# ExternalConnectors.net
KiCad netlist of a schematic drawn in Altium Designer
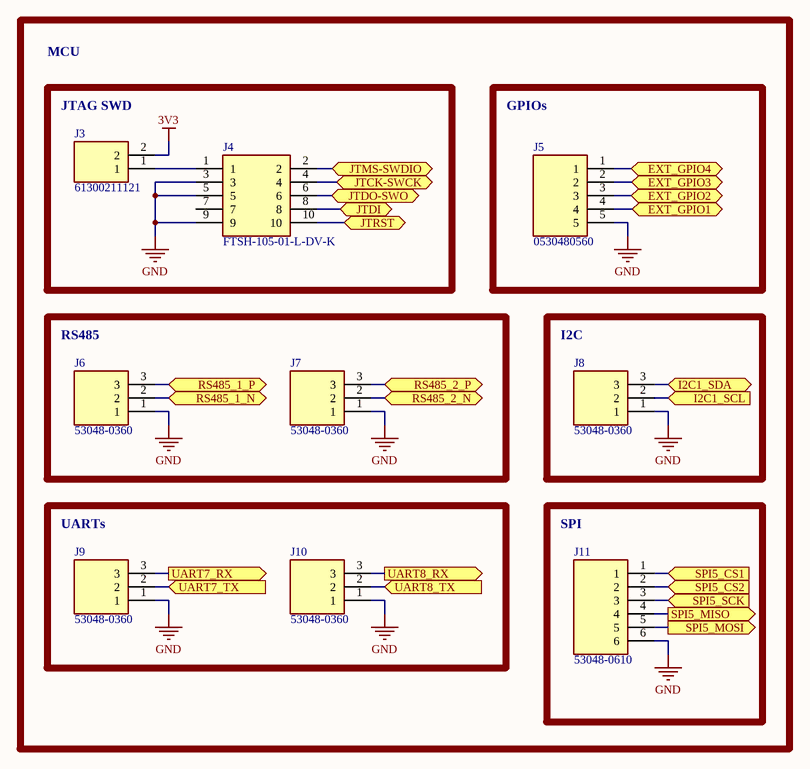
[diagram p0: ExternalConnectors.SchDoc]

(export (version "E")
  (design (tool "Eeschema 10.0.6"))
  (components
    (comp (ref "J3")
      (value "61300211121")
      (footprint "RT_IS:HDRV2W110P0X254_1X2_508X254X854P")
      (description "Connector")
      (fields (field (name "MOUSER PART NUMBER") "710-61300211121"))
      (libsource (lib "*") (part "61300211121"))
    )
    (comp (ref "J4")
      (value "FTSH-105-01-L-DV-K")
      (footprint "RT_IS:FTSH10501LDVK")
      (description "Connector Header Surface Mount 10 position 0.050\" (1.27mm)")
      (fields (field (name "MOUSER PART NUMBER") "200-FTSH10501LDVK"))
      (libsource (lib "*") (part "FTSH-105-01-L-DV-K"))
    )
    (comp (ref "J5")
      (value "0530480560")
      (footprint "RT_IS:530480510")
      (description "Connector Header Through Hole, Right Angle 5 position 0.049\" (1.25mm)")
      (fields
        (field (name "MANUFACTURER_PART_NUMBER") "53048-0510")
        (field (name "MOUSER PART NUMBER") "538-53048-0510")
      )
      (libsource (lib "*") (part "53048-0510"))
    )
    (comp (ref "J6")
      (value "53048-0360")
      (footprint "RT_IS:SHDRRA3W35P0X125_1X3_550X550X350P")
      (description "Connector Header Through Hole, Right Angle 3 position 0.049\" (1.25mm)")
      (fields
        (field (name "MANUFACTURER_PART_NUMBER") "53048-0310")
        (field (name "MOUSER PART NUMBER") "538-53048-0310")
      )
      (libsource (lib "*") (part "53048-0310"))
    )
    (comp (ref "J7")
      (value "53048-0360")
      (footprint "RT_IS:SHDRRA3W35P0X125_1X3_550X550X350P")
      (description "Connector Header Through Hole, Right Angle 3 position 0.049\" (1.25mm)")
      (fields
        (field (name "MANUFACTURER_PART_NUMBER") "53048-0310")
        (field (name "MOUSER PART NUMBER") "538-53048-0310")
      )
      (libsource (lib "*") (part "53048-0310"))
    )
    (comp (ref "J8")
      (value "53048-0360")
      (footprint "RT_IS:SHDRRA3W35P0X125_1X3_550X550X350P")
      (description "Connector Header Through Hole, Right Angle 3 position 0.049\" (1.25mm)")
      (fields
        (field (name "MANUFACTURER_PART_NUMBER") "53048-0310")
        (field (name "MOUSER PART NUMBER") "538-53048-0310")
      )
      (libsource (lib "*") (part "53048-0310"))
    )
    (comp (ref "J9")
      (value "53048-0360")
      (footprint "RT_IS:SHDRRA3W35P0X125_1X3_550X550X350P")
      (description "Connector Header Through Hole, Right Angle 3 position 0.049\" (1.25mm)")
      (fields
        (field (name "MANUFACTURER_PART_NUMBER") "53048-0310")
        (field (name "MOUSER PART NUMBER") "538-53048-0310")
      )
      (libsource (lib "*") (part "53048-0310"))
    )
    (comp (ref "J10")
      (value "53048-0360")
      (footprint "RT_IS:SHDRRA3W35P0X125_1X3_550X550X350P")
      (description "Connector Header Through Hole, Right Angle 3 position 0.049\" (1.25mm)")
      (fields
        (field (name "MANUFACTURER_PART_NUMBER") "53048-0310")
        (field (name "MOUSER PART NUMBER") "538-53048-0310")
      )
      (libsource (lib "*") (part "53048-0310"))
    )
    (comp (ref "J11")
      (value "53048-0610")
      (footprint "530480610")
      (description "Connector")
      (fields (field (name "MOUSER PART NUMBER") "538-53048-0610"))
      (libsource (lib "*") (part "53048-0610"))
    )
  )
  (nets
    (net (code "1") (name "/EXT_GPIO1") (class "Default")
      (node (ref "J5") (pin "4") (pinfunction "4_4") (pintype "passive"))
    )
    (net (code "2") (name "/EXT_GPIO2") (class "Default")
      (node (ref "J5") (pin "3") (pinfunction "3_3") (pintype "passive"))
    )
    (net (code "3") (name "/EXT_GPIO3") (class "Default")
      (node (ref "J5") (pin "2") (pinfunction "2_2") (pintype "passive"))
    )
    (net (code "4") (name "/EXT_GPIO4") (class "Default")
      (node (ref "J5") (pin "1") (pinfunction "1_1") (pintype "passive"))
    )
    (net (code "5") (name "/I2C1_SCL") (class "Default")
      (node (ref "J8") (pin "2") (pinfunction "2_2") (pintype "passive"))
    )
    (net (code "6") (name "/I2C1_SDA") (class "Default")
      (node (ref "J8") (pin "3") (pinfunction "3_3") (pintype "passive"))
    )
    (net (code "7") (name "/JTCK-SWCK") (class "Default")
      (node (ref "J4") (pin "4") (pinfunction "4_4") (pintype "passive"))
    )
    (net (code "8") (name "/JTDI") (class "Default")
      (node (ref "J4") (pin "8") (pinfunction "8_8") (pintype "passive"))
    )
    (net (code "9") (name "/JTDO-SWO") (class "Default")
      (node (ref "J4") (pin "6") (pinfunction "6_6") (pintype "passive"))
    )
    (net (code "10") (name "/JTMS-SWDIO") (class "Default")
      (node (ref "J4") (pin "2") (pinfunction "2_2") (pintype "passive"))
    )
    (net (code "11") (name "/JTRST") (class "Default")
      (node (ref "J4") (pin "10") (pinfunction "10_10") (pintype "passive"))
    )
    (net (code "12") (name "/RS485_1_N") (class "Default")
      (node (ref "J6") (pin "2") (pinfunction "2_2") (pintype "passive"))
    )
    (net (code "13") (name "/RS485_1_P") (class "Default")
      (node (ref "J6") (pin "3") (pinfunction "3_3") (pintype "passive"))
    )
    (net (code "14") (name "/RS485_2_N") (class "Default")
      (node (ref "J7") (pin "2") (pinfunction "2_2") (pintype "passive"))
    )
    (net (code "15") (name "/RS485_2_P") (class "Default")
      (node (ref "J7") (pin "3") (pinfunction "3_3") (pintype "passive"))
    )
    (net (code "16") (name "/SPI5_CS1") (class "Default")
      (node (ref "J11") (pin "1") (pinfunction "1_1") (pintype "passive"))
    )
    (net (code "17") (name "/SPI5_CS2") (class "Default")
      (node (ref "J11") (pin "2") (pinfunction "2_2") (pintype "passive"))
    )
    (net (code "18") (name "/SPI5_MISO") (class "Default")
      (node (ref "J11") (pin "4") (pinfunction "4_4") (pintype "passive"))
    )
    (net (code "19") (name "/SPI5_MOSI") (class "Default")
      (node (ref "J11") (pin "5") (pinfunction "5_5") (pintype "passive"))
    )
    (net (code "20") (name "/SPI5_SCK") (class "Default")
      (node (ref "J11") (pin "3") (pinfunction "3_3") (pintype "passive"))
    )
    (net (code "21") (name "/UART7_RX") (class "Default")
      (node (ref "J9") (pin "3") (pinfunction "3_3") (pintype "passive"))
    )
    (net (code "22") (name "/UART7_TX") (class "Default")
      (node (ref "J9") (pin "2") (pinfunction "2_2") (pintype "passive"))
    )
    (net (code "23") (name "/UART8_RX") (class "Default")
      (node (ref "J10") (pin "3") (pinfunction "3_3") (pintype "passive"))
    )
    (net (code "24") (name "/UART8_TX") (class "Default")
      (node (ref "J10") (pin "2") (pinfunction "2_2") (pintype "passive"))
    )
    (net (code "25") (name "3V3") (class "Default")
      (node (ref "J3") (pin "2") (pinfunction "2_2") (pintype "passive"))
    )
    (net (code "26") (name "GND") (class "Default")
      (node (ref "J10") (pin "1") (pinfunction "1_1") (pintype "passive"))
      (node (ref "J11") (pin "6") (pinfunction "6_6") (pintype "passive"))
      (node (ref "J4") (pin "3") (pinfunction "3_3") (pintype "passive"))
      (node (ref "J4") (pin "5") (pinfunction "5_5") (pintype "passive"))
      (node (ref "J4") (pin "9") (pinfunction "9_9") (pintype "passive"))
      (node (ref "J5") (pin "5") (pinfunction "5_5") (pintype "passive"))
      (node (ref "J6") (pin "1") (pinfunction "1_1") (pintype "passive"))
      (node (ref "J7") (pin "1") (pinfunction "1_1") (pintype "passive"))
      (node (ref "J8") (pin "1") (pinfunction "1_1") (pintype "passive"))
      (node (ref "J9") (pin "1") (pinfunction "1_1") (pintype "passive"))
    )
    (net (code "27") (name "Net-(J3-Pad1)") (class "Default")
      (node (ref "J3") (pin "1") (pinfunction "1_1") (pintype "passive"))
      (node (ref "J4") (pin "1") (pinfunction "1_1") (pintype "passive"))
    )
    (net (code "28") (name "unconnected-(J4-Pad7)") (class "Default")
      (node (ref "J4") (pin "7") (pinfunction "7_7") (pintype "passive"))
    )
  )
)
